# dreamcast-universal-power-supply.net
KiCad netlist of a schematic drawn in EAGLE
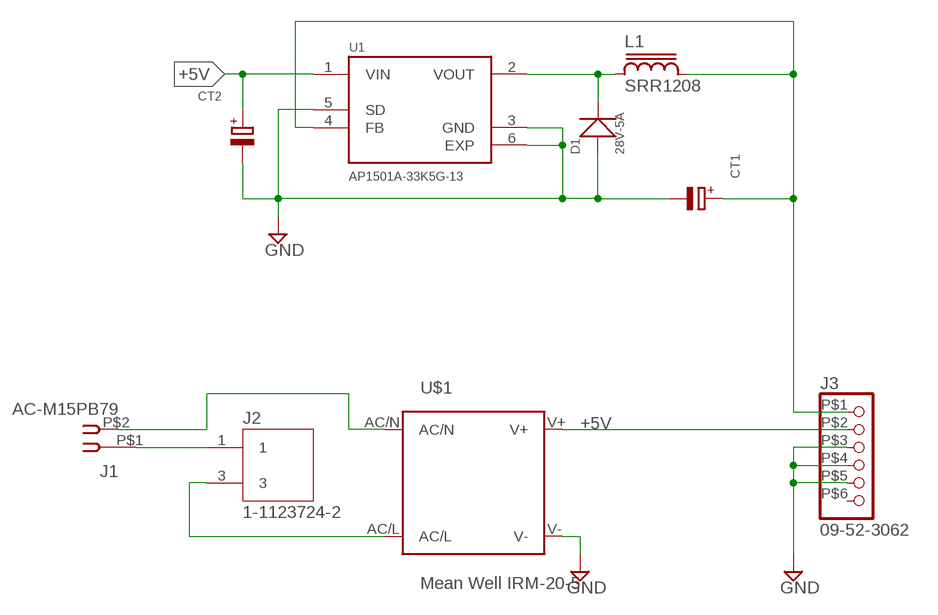
[diagram p0: schematic, sheet 1]

(export (version "E")
  (design (tool "Eeschema 10.0.6"))
  (components
    (comp (ref "CT1")
      (value "C-POL_ECAP-8.5MM")
      (footprint "eagle-import:CAPAE830X1050N")
      (libsource (lib "eagle-import") (part "C-POLECAP-8.5MM_"))
    )
    (comp (ref "CT2")
      (value "C-POL_ECAP-8.5MM")
      (footprint "eagle-import:CAPAE830X1050N")
      (libsource (lib "eagle-import") (part "C-POLECAP-8.5MM_"))
    )
    (comp (ref "D1")
      (value "28V-5A")
      (footprint "eagle-import:DO-214AA")
      (fields (field (name "MPN") "SS54B"))
      (libsource (lib "eagle-import") (part "SMD-DIODE-SCHOTTKY-28V-5A(DO-214AA)"))
    )
    (comp (ref "J1")
      (value "AC-M15PB79")
      (footprint "eagle-import:AC-M15PB79")
      (libsource (lib "eagle-import") (part "AC-M15PB79"))
    )
    (comp (ref "J2")
      (value "1-1123724-2")
      (footprint "eagle-import:TE_1-1123724-2")
      (fields (field (name "MF") "TE Connectivity"))
      (libsource (lib "eagle-import") (part "1-1123724-2"))
    )
    (comp (ref "J3")
      (value "09-52-3062")
      (footprint "eagle-import:09-52-3062")
      (libsource (lib "eagle-import") (part "09-52-3062"))
    )
    (comp (ref "L1")
      (value "SRR1208")
      (footprint "eagle-import:SSR1208")
      (libsource (lib "eagle-import") (part "SRR1208"))
    )
    (comp (ref "U$1")
      (value "Mean Well IRM-20-5")
      (footprint "eagle-import:IRM_15_20")
      (libsource (lib "eagle-import") (part "IRM_15/20IRM_15/20"))
    )
    (comp (ref "U1")
      (value "AP1501A-33K5G-13")
      (footprint "eagle-import:DPAK171P1524X485-6N")
      (fields (field (name "MF") "Diodes Inc."))
      (libsource (lib "eagle-import") (part "AP1501A-33K5G-13"))
    )
  )
  (nets
    (net (code "1") (name "+5V") (class "Default")
      (node (ref "CT2") (pin "1") (pinfunction "+_1") (pintype "passive"))
      (node (ref "J3") (pin "P$2") (pinfunction "2_P$2") (pintype "passive"))
      (node (ref "U$1") (pin "V+") (pinfunction "V+_V+") (pintype "output"))
      (node (ref "U1") (pin "1") (pinfunction "VIN_1") (pintype "input"))
    )
    (net (code "2") (name "GND") (class "Default")
      (node (ref "CT1") (pin "2") (pinfunction "-_2") (pintype "passive"))
      (node (ref "CT2") (pin "2") (pinfunction "-_2") (pintype "passive"))
      (node (ref "D1") (pin "+") (pinfunction "+_+") (pintype "passive"))
      (node (ref "J3") (pin "P$3") (pinfunction "3_P$3") (pintype "passive"))
      (node (ref "J3") (pin "P$4") (pinfunction "4_P$4") (pintype "passive"))
      (node (ref "J3") (pin "P$5") (pinfunction "5_P$5") (pintype "passive"))
      (node (ref "U$1") (pin "V-") (pinfunction "V-_V-") (pintype "output"))
      (node (ref "U1") (pin "3") (pinfunction "GND_3") (pintype "power_in"))
      (node (ref "U1") (pin "5") (pinfunction "SD_5") (pintype "input"))
      (node (ref "U1") (pin "6") (pinfunction "EXP_6") (pintype "power_in"))
    )
    (net (code "3") (name "Net-(CT1-+)") (class "Default")
      (node (ref "CT1") (pin "1") (pinfunction "+_1") (pintype "passive"))
      (node (ref "J3") (pin "P$1") (pinfunction "1_P$1") (pintype "passive"))
      (node (ref "L1") (pin "2") (pinfunction "2_2") (pintype "passive"))
      (node (ref "U1") (pin "4") (pinfunction "FB_4") (pintype "input"))
    )
    (net (code "4") (name "Net-(J1-1)") (class "Default")
      (node (ref "J1") (pin "P$1") (pinfunction "1_P$1") (pintype "power_in"))
      (node (ref "J2") (pin "1") (pinfunction "1_1") (pintype "passive"))
    )
    (net (code "5") (name "Net-(J1-2)") (class "Default")
      (node (ref "J1") (pin "P$2") (pinfunction "2_P$2") (pintype "power_in"))
      (node (ref "U$1") (pin "AC/N") (pinfunction "AC/N_AC/N") (pintype "input"))
    )
    (net (code "6") (name "Net-(J2-Pad3)") (class "Default")
      (node (ref "J2") (pin "3") (pinfunction "3_3") (pintype "passive"))
      (node (ref "U$1") (pin "AC/L") (pinfunction "AC/L_AC/L") (pintype "input"))
    )
    (net (code "7") (name "Net-(U1-VOUT)") (class "Default")
      (node (ref "D1") (pin "-") (pinfunction "-_-") (pintype "passive"))
      (node (ref "L1") (pin "1") (pinfunction "1_1") (pintype "passive"))
      (node (ref "U1") (pin "2") (pinfunction "VOUT_2") (pintype "output"))
    )
    (net (code "8") (name "unconnected-(J3-6-PadP$6)") (class "Default")
      (node (ref "J3") (pin "P$6") (pinfunction "6_P$6") (pintype "passive"))
    )
  )
)
